# CPU_STM32F7.net
KiCad netlist of a schematic drawn in Altium Designer
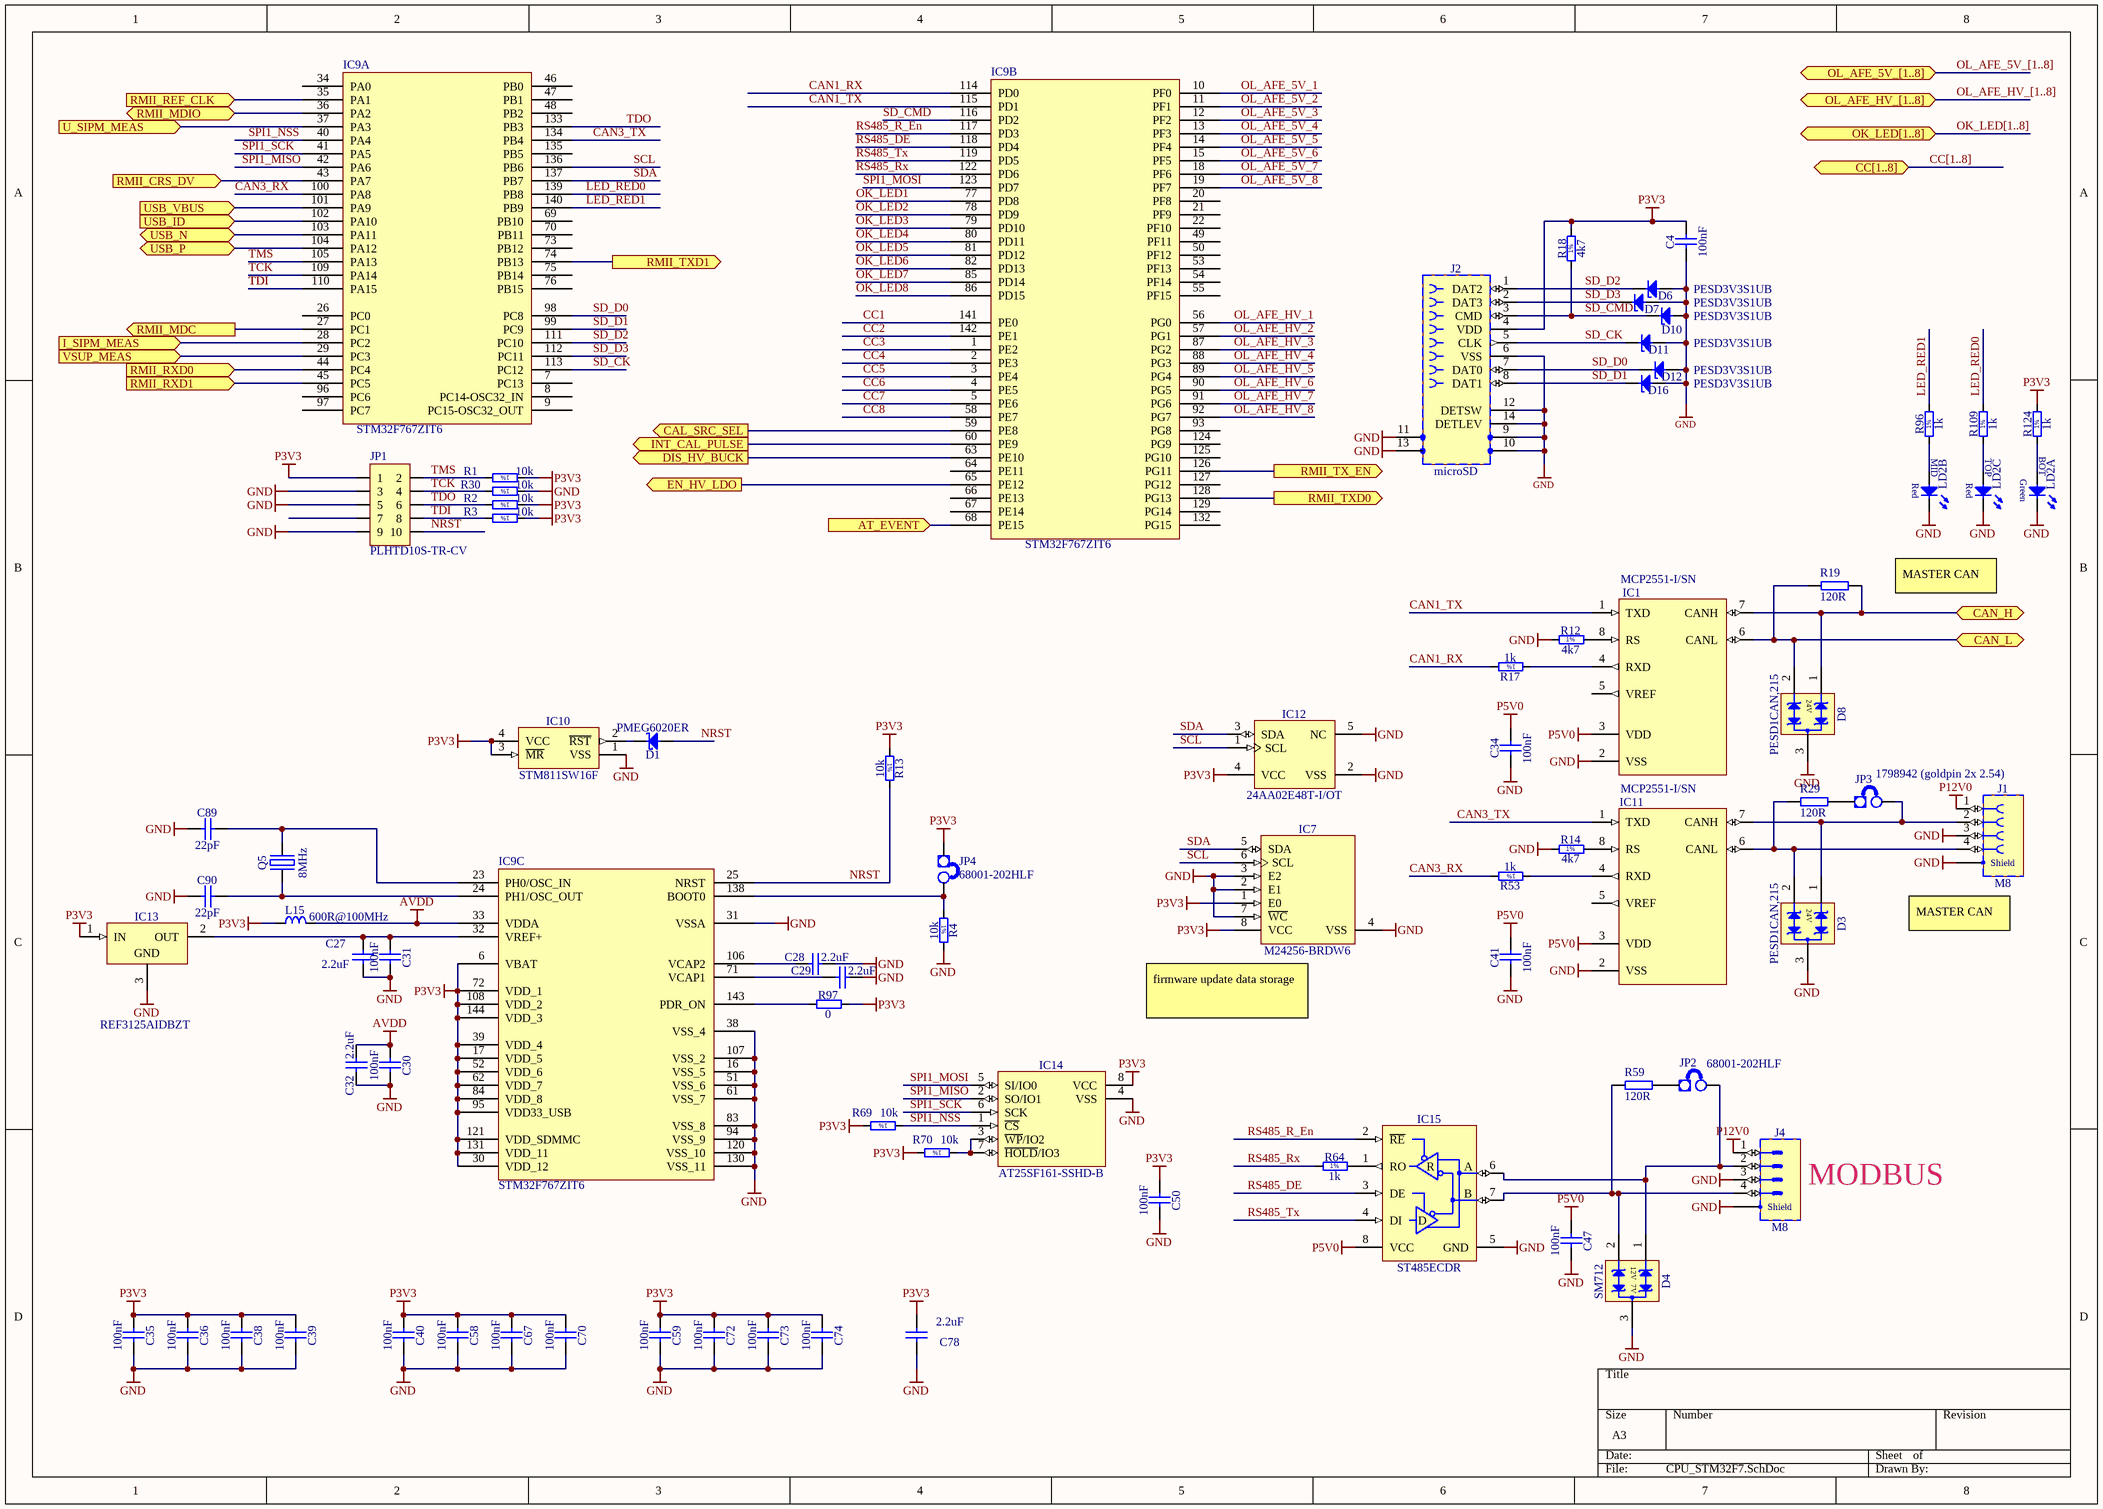
[diagram p0: CPU_STM32F7.SchDoc]

(export (version "E")
  (design (tool "Eeschema 10.0.6"))
  (components
    (comp (ref "C4")
      (value "100nF")
      (footprint "CAPC1005X55N")
      (description "Non-polarised capacitor")
      (fields
        (field (name "PART NUMBER") "CC0402_100NF_16V_10%_X7R")
        (field (name "VOLTAGE") "16V")
        (field (name "AUTHOR") "CERN DEM JLC")
      )
      (libsource (lib "Capacitors") (part "Capacitor - non polarized"))
    )
    (comp (ref "C27")
      (value "2.2uF")
      (footprint "CAPC1608X90N")
      (description "Non-polarised capacitor")
      (fields
        (field (name "PART NUMBER") "CC0603_2.2UF_10V_20%_X7R")
        (field (name "VOLTAGE") "10V")
        (field (name "AUTHOR") "CERN DEM JLC")
      )
      (libsource (lib "Capacitors") (part "Capacitor - non polarized"))
    )
    (comp (ref "C28")
      (value "2.2uF")
      (footprint "CAPC1608X90N")
      (description "Non-polarised capacitor")
      (fields
        (field (name "PART NUMBER") "CC0603_2.2UF_10V_20%_X7R")
        (field (name "VOLTAGE") "10V")
        (field (name "AUTHOR") "CERN DEM JLC")
      )
      (libsource (lib "Capacitors") (part "Capacitor - non polarized"))
    )
    (comp (ref "C29")
      (value "2.2uF")
      (footprint "CAPC1608X90N")
      (description "Non-polarised capacitor")
      (fields
        (field (name "PART NUMBER") "CC0603_2.2UF_10V_20%_X7R")
        (field (name "VOLTAGE") "10V")
        (field (name "AUTHOR") "CERN DEM JLC")
      )
      (libsource (lib "Capacitors") (part "Capacitor - non polarized"))
    )
    (comp (ref "C30")
      (value "100nF")
      (footprint "CAPC1005X55N")
      (description "Non-polarised capacitor")
      (fields
        (field (name "PART NUMBER") "CC0402_100NF_16V_10%_X7R")
        (field (name "VOLTAGE") "16V")
        (field (name "AUTHOR") "CERN DEM JLC")
      )
      (libsource (lib "Capacitors") (part "Capacitor - non polarized"))
    )
    (comp (ref "C31")
      (value "100nF")
      (footprint "CAPC1005X55N")
      (description "Non-polarised capacitor")
      (fields
        (field (name "PART NUMBER") "CC0402_100NF_16V_10%_X7R")
        (field (name "VOLTAGE") "16V")
        (field (name "AUTHOR") "CERN DEM JLC")
      )
      (libsource (lib "Capacitors") (part "Capacitor - non polarized"))
    )
    (comp (ref "C32")
      (value "2.2uF")
      (footprint "CAPC1608X90N")
      (description "Non-polarised capacitor")
      (fields
        (field (name "PART NUMBER") "CC0603_2.2UF_10V_20%_X7R")
        (field (name "VOLTAGE") "10V")
        (field (name "AUTHOR") "CERN DEM JLC")
      )
      (libsource (lib "Capacitors") (part "Capacitor - non polarized"))
    )
    (comp (ref "C34")
      (value "100nF")
      (footprint "CAPC1005X55N")
      (description "Non-polarised capacitor")
      (fields
        (field (name "PART NUMBER") "CC0402_100NF_16V_10%_X7R")
        (field (name "VOLTAGE") "16V")
        (field (name "AUTHOR") "CERN DEM JLC")
      )
      (libsource (lib "Capacitors") (part "Capacitor - non polarized"))
    )
    (comp (ref "C35")
      (value "100nF")
      (footprint "CAPC1005X55N")
      (description "Non-polarised capacitor")
      (fields
        (field (name "PART NUMBER") "CC0402_100NF_16V_10%_X7R")
        (field (name "VOLTAGE") "16V")
        (field (name "AUTHOR") "CERN DEM JLC")
      )
      (libsource (lib "Capacitors") (part "Capacitor - non polarized"))
    )
    (comp (ref "C36")
      (value "100nF")
      (footprint "CAPC1005X55N")
      (description "Non-polarised capacitor")
      (fields
        (field (name "PART NUMBER") "CC0402_100NF_16V_10%_X7R")
        (field (name "VOLTAGE") "16V")
        (field (name "AUTHOR") "CERN DEM JLC")
      )
      (libsource (lib "Capacitors") (part "Capacitor - non polarized"))
    )
    (comp (ref "C38")
      (value "100nF")
      (footprint "CAPC1005X55N")
      (description "Non-polarised capacitor")
      (fields
        (field (name "PART NUMBER") "CC0402_100NF_16V_10%_X7R")
        (field (name "VOLTAGE") "16V")
        (field (name "AUTHOR") "CERN DEM JLC")
      )
      (libsource (lib "Capacitors") (part "Capacitor - non polarized"))
    )
    (comp (ref "C39")
      (value "100nF")
      (footprint "CAPC1005X55N")
      (description "Non-polarised capacitor")
      (fields
        (field (name "PART NUMBER") "CC0402_100NF_16V_10%_X7R")
        (field (name "VOLTAGE") "16V")
        (field (name "AUTHOR") "CERN DEM JLC")
      )
      (libsource (lib "Capacitors") (part "Capacitor - non polarized"))
    )
    (comp (ref "C40")
      (value "100nF")
      (footprint "CAPC1005X55N")
      (description "Non-polarised capacitor")
      (fields
        (field (name "PART NUMBER") "CC0402_100NF_16V_10%_X7R")
        (field (name "VOLTAGE") "16V")
        (field (name "AUTHOR") "CERN DEM JLC")
      )
      (libsource (lib "Capacitors") (part "Capacitor - non polarized"))
    )
    (comp (ref "C41")
      (value "100nF")
      (footprint "CAPC1005X55N")
      (description "Non-polarised capacitor")
      (fields
        (field (name "PART NUMBER") "CC0402_100NF_16V_10%_X7R")
        (field (name "VOLTAGE") "16V")
        (field (name "AUTHOR") "CERN DEM JLC")
      )
      (libsource (lib "Capacitors") (part "Capacitor - non polarized"))
    )
    (comp (ref "C47")
      (value "100nF")
      (footprint "CAPC1005X55N")
      (description "Non-polarised capacitor")
      (fields
        (field (name "PART NUMBER") "CC0402_100NF_16V_10%_X7R")
        (field (name "VOLTAGE") "16V")
        (field (name "AUTHOR") "CERN DEM JLC")
      )
      (libsource (lib "Capacitors") (part "Capacitor - non polarized"))
    )
    (comp (ref "C50")
      (value "100nF")
      (footprint "CAPC1005X55N")
      (description "Non-polarised capacitor")
      (fields
        (field (name "PART NUMBER") "CC0402_100NF_16V_10%_X7R")
        (field (name "VOLTAGE") "16V")
        (field (name "AUTHOR") "CERN DEM JLC")
      )
      (libsource (lib "Capacitors") (part "Capacitor - non polarized"))
    )
    (comp (ref "C58")
      (value "100nF")
      (footprint "CAPC1005X55N")
      (description "Non-polarised capacitor")
      (fields
        (field (name "PART NUMBER") "CC0402_100NF_16V_10%_X7R")
        (field (name "VOLTAGE") "16V")
        (field (name "AUTHOR") "CERN DEM JLC")
      )
      (libsource (lib "Capacitors") (part "Capacitor - non polarized"))
    )
    (comp (ref "C59")
      (value "100nF")
      (footprint "CAPC1005X55N")
      (description "Non-polarised capacitor")
      (fields
        (field (name "PART NUMBER") "CC0402_100NF_16V_10%_X7R")
        (field (name "VOLTAGE") "16V")
        (field (name "AUTHOR") "CERN DEM JLC")
      )
      (libsource (lib "Capacitors") (part "Capacitor - non polarized"))
    )
    (comp (ref "C67")
      (value "100nF")
      (footprint "CAPC1005X55N")
      (description "Non-polarised capacitor")
      (fields
        (field (name "PART NUMBER") "CC0402_100NF_16V_10%_X7R")
        (field (name "VOLTAGE") "16V")
        (field (name "AUTHOR") "CERN DEM JLC")
      )
      (libsource (lib "Capacitors") (part "Capacitor - non polarized"))
    )
    (comp (ref "C70")
      (value "100nF")
      (footprint "CAPC1005X55N")
      (description "Non-polarised capacitor")
      (fields
        (field (name "PART NUMBER") "CC0402_100NF_16V_10%_X7R")
        (field (name "VOLTAGE") "16V")
        (field (name "AUTHOR") "CERN DEM JLC")
      )
      (libsource (lib "Capacitors") (part "Capacitor - non polarized"))
    )
    (comp (ref "C72")
      (value "100nF")
      (footprint "CAPC1005X55N")
      (description "Non-polarised capacitor")
      (fields
        (field (name "PART NUMBER") "CC0402_100NF_16V_10%_X7R")
        (field (name "VOLTAGE") "16V")
        (field (name "AUTHOR") "CERN DEM JLC")
      )
      (libsource (lib "Capacitors") (part "Capacitor - non polarized"))
    )
    (comp (ref "C73")
      (value "100nF")
      (footprint "CAPC1005X55N")
      (description "Non-polarised capacitor")
      (fields
        (field (name "PART NUMBER") "CC0402_100NF_16V_10%_X7R")
        (field (name "VOLTAGE") "16V")
        (field (name "AUTHOR") "CERN DEM JLC")
      )
      (libsource (lib "Capacitors") (part "Capacitor - non polarized"))
    )
    (comp (ref "C74")
      (value "100nF")
      (footprint "CAPC1005X55N")
      (description "Non-polarised capacitor")
      (fields
        (field (name "PART NUMBER") "CC0402_100NF_16V_10%_X7R")
        (field (name "VOLTAGE") "16V")
        (field (name "AUTHOR") "CERN DEM JLC")
      )
      (libsource (lib "Capacitors") (part "Capacitor - non polarized"))
    )
    (comp (ref "C78")
      (value "2.2uF")
      (footprint "CAPC1608X90N")
      (description "Non-polarised capacitor")
      (fields
        (field (name "PART NUMBER") "CC0603_2.2UF_10V_20%_X7R")
        (field (name "VOLTAGE") "10V")
        (field (name "AUTHOR") "CERN DEM JLC")
      )
      (libsource (lib "Capacitors") (part "Capacitor - non polarized"))
    )
    (comp (ref "C89")
      (value "22pF")
      (footprint "CAPC1005X55N")
      (description "Non-polarised capacitor")
      (fields
        (field (name "PART NUMBER") "CC0402_22PF_50V_5%_C0G")
        (field (name "VOLTAGE") "50V")
        (field (name "AUTHOR") "CERN DEM JLC")
      )
      (libsource (lib "Capacitors") (part "Capacitor - non polarized"))
    )
    (comp (ref "C90")
      (value "22pF")
      (footprint "CAPC1005X55N")
      (description "Non-polarised capacitor")
      (fields
        (field (name "PART NUMBER") "CC0402_22PF_50V_5%_C0G")
        (field (name "VOLTAGE") "50V")
        (field (name "AUTHOR") "CERN DEM JLC")
      )
      (libsource (lib "Capacitors") (part "Capacitor - non polarized"))
    )
    (comp (ref "D1")
      (value "PMEG6020ER")
      (footprint "SODFL3517X110N")
      (description "Schottky Diode")
      (fields
        (field (name "VOLTAGE") "60V")
        (field (name "POWER") "2A")
        (field (name "AUTHOR") "CERN DEM JMW")
      )
      (libsource (lib "ICs And Semiconductors") (part "Diode Schottky"))
    )
    (comp (ref "D3")
      (value "PESD1CAN,215")
      (footprint "SOT95P237X112-3N")
      (description "TVS Diode for CAN")
      (fields
        (field (name "VOLTAGE") "24V")
        (field (name "POWER") "400W")
        (field (name "AUTHOR") "CERN DEM JLC")
      )
      (libsource (lib "Diodes") (part "D_TVS_PESD1CAN"))
    )
    (comp (ref "D4")
      (value "SM712")
      (footprint "SOT95P237X112-3N")
      (description "Asymmetrical TVS Diode for Extended Common-Mode RS-485")
      (fields
        (field (name "VOLTAGE") "12V/-7V")
        (field (name "POWER") "400W")
        (field (name "AUTHOR") "CERN DEM JLC")
      )
      (libsource (lib "ICs And Semiconductors") (part "SM712"))
    )
    (comp (ref "D6")
      (value "PESD3V3S1UB")
      (footprint "SODFL1608X65N")
      (description "ESD protection diode")
      (fields
        (field (name "VOLTAGE") "3V3")
        (field (name "POWER") "330W")
        (field (name "AUTHOR") "CERN DEM JLC")
      )
      (libsource (lib "ICs And Semiconductors") (part "Diode ESD"))
    )
    (comp (ref "D7")
      (value "PESD3V3S1UB")
      (footprint "SODFL1608X65N")
      (description "ESD protection diode")
      (fields
        (field (name "VOLTAGE") "3V3")
        (field (name "POWER") "330W")
        (field (name "AUTHOR") "CERN DEM JLC")
      )
      (libsource (lib "ICs And Semiconductors") (part "Diode ESD"))
    )
    (comp (ref "D8")
      (value "PESD1CAN,215")
      (footprint "SOT95P237X112-3N")
      (description "TVS Diode for CAN")
      (fields
        (field (name "VOLTAGE") "24V")
        (field (name "POWER") "400W")
        (field (name "AUTHOR") "CERN DEM JLC")
      )
      (libsource (lib "Diodes") (part "D_TVS_PESD1CAN"))
    )
    (comp (ref "D10")
      (value "PESD3V3S1UB")
      (footprint "SODFL1608X65N")
      (description "ESD protection diode")
      (fields
        (field (name "VOLTAGE") "3V3")
        (field (name "POWER") "330W")
        (field (name "AUTHOR") "CERN DEM JLC")
      )
      (libsource (lib "ICs And Semiconductors") (part "Diode ESD"))
    )
    (comp (ref "D11")
      (value "PESD3V3S1UB")
      (footprint "SODFL1608X65N")
      (description "ESD protection diode")
      (fields
        (field (name "VOLTAGE") "3V3")
        (field (name "POWER") "330W")
        (field (name "AUTHOR") "CERN DEM JLC")
      )
      (libsource (lib "ICs And Semiconductors") (part "Diode ESD"))
    )
    (comp (ref "D12")
      (value "PESD3V3S1UB")
      (footprint "SODFL1608X65N")
      (description "ESD protection diode")
      (fields
        (field (name "VOLTAGE") "3V3")
        (field (name "POWER") "330W")
        (field (name "AUTHOR") "CERN DEM JLC")
      )
      (libsource (lib "ICs And Semiconductors") (part "Diode ESD"))
    )
    (comp (ref "D16")
      (value "PESD3V3S1UB")
      (footprint "SODFL1608X65N")
      (description "ESD protection diode")
      (fields
        (field (name "VOLTAGE") "3V3")
        (field (name "POWER") "330W")
        (field (name "AUTHOR") "CERN DEM JLC")
      )
      (libsource (lib "ICs And Semiconductors") (part "Diode ESD"))
    )
    (comp (ref "IC1")
      (value "MCP2551-I/SN")
      (footprint "SOIC127P600X175-8N")
      (description "High-Speed CAN Transceiver, 8-Pin SOIC, Industrial Temperature")
      (fields (field (name "MANUFACTURER") "MICROCHIP TECHNOLOGY") (field (name "AUTHOR") "GK"))
      (libsource (lib "LIBRARY_SCH") (part "IFC_MCP2551"))
    )
    (comp (ref "IC7")
      (value "M24256-BRDW6")
      (footprint "SOP65P640X120-8N")
      (description "256-Kbit Serial I²C Bus EEPROM")
      (fields
        (field (name "PART NUMBER") "M24256-BRDW6P")
        (field (name "MANUFACTURER") "ST MICROELECTRONICS")
        (field (name "AUTHOR") "CERN DEM MR")
      )
      (libsource (lib "LIBRARY_SCH") (part "MEM_M24256-BRDW6P"))
    )
    (comp (ref "IC9")
      (value "STM32F767ZIT6")
      (footprint "TSQFP50P2200X2200X160-144N")
      (description "32-bit Arm® Cortex-M7 216MHz MCUs, 2MB Flash,\r\n512kB RAM, 28 com. and analog interfaces")
      (libsource (lib "ICS_CPU") (part "UPC_STM32F767ZIT6"))
    )
    (comp (ref "IC10")
      (value "STM811SW16F")
      (footprint "SOT143N")
      (description "Microprocessor Reset Circuit")
      (fields (field (name "MANUFACTURER") "ST MICROELECTRONICS") (field (name "AUTHOR") "CERN DEM JLC"))
      (libsource (lib "ICs And Semiconductors") (part "STM811"))
    )
    (comp (ref "IC11")
      (value "MCP2551-I/SN")
      (footprint "SOIC127P600X175-8N")
      (description "High-Speed CAN Transceiver, 8-Pin SOIC, Industrial Temperature")
      (fields (field (name "MANUFACTURER") "MICROCHIP TECHNOLOGY") (field (name "AUTHOR") "GK"))
      (libsource (lib "LIBRARY_SCH") (part "IFC_MCP2551"))
    )
    (comp (ref "IC12")
      (value "24AA02E48T-I/OT")
      (footprint "SOT95P280X145-5N")
      (description "1.7V-5.5V, 2K I2C Serial EEPROM With EUI-48 Node Identity")
      (fields (field (name "MANUFACTURER") "MICROCHIP TECHNOLOGY") (field (name "AUTHOR") "CERN DEM MR"))
      (libsource (lib "ICs And Semiconductors") (part "24AA02E48T-I/OT"))
    )
    (comp (ref "IC13")
      (value "REF3125AIDBZT")
      (footprint "SOT95P237X112-3N")
      (description "3-Terminal Regulator 1=IN 2=OUT 3=GND")
      (fields (field (name "MANUFACTURER") "TEXAS INSTRUMENTS") (field (name "AUTHOR") "CERN DEM MR"))
      (libsource (lib "ICs And Semiconductors") (part "REG3 1IN-2OUT-3GND"))
    )
    (comp (ref "IC14")
      (value "AT25SF161-SSHD-B")
      (footprint "SOIC127P790X216-8N")
      (description "16Mb, 3V, Multiple I/O Serial NOR Flash Memory")
      (fields (field (name "AUTHOR") "GK"))
      (libsource (lib "LIBRARY_SCH") (part "MEM_AT25SF161"))
    )
    (comp (ref "IC15")
      (value "ST485ECDR")
      (footprint "SOIC127P600X175-8N")
      (description "±15kV ESD-Protected, Low Power  RS-485/RS-422 Transceiver")
      (fields (field (name "MANUFACTURER") "ST MICROELECTRONICS") (field (name "AUTHOR") "CERN DEM MR"))
      (libsource (lib "ICs And Semiconductors") (part "ST485EC"))
    )
    (comp (ref "J1")
      (value "M8")
      (footprint "AMPHENOL_M8AS-04PFFR-SF8001")
      (description "Connector 4 Female + Shield")
      (fields
        (field (name "PART NUMBER") "AMPHENOL_M8AS-04PFFR-SF8001")
        (field (name "MANUFACTURER") "AMPHENOL")
        (field (name "AUTHOR") "CERN DEM MR")
      )
      (libsource (lib "Connectors") (part "Connector 4 Female + Shield"))
    )
    (comp (ref "J2")
      (value "microSD")
      (footprint "MOLEX_502570-0893")
      (description "Connector MicroSD 8 Pin")
      (fields
        (field (name "PART NUMBER") "MOLEX_502570-0893")
        (field (name "MANUFACTURER") "MOLEX")
        (field (name "AUTHOR") "CERN DEM JLC")
      )
      (libsource (lib "Connectors") (part "MOLEX_502570-0893"))
    )
    (comp (ref "J4")
      (value "M8")
      (footprint "AMPHENOL_M8AS-04PMMR-SF8001")
      (description "Connector 4 Male + Shield")
      (fields
        (field (name "PART NUMBER") "AMPHENOL_M8AS-04PMMR-SF8001")
        (field (name "MANUFACTURER") "AMPHENOL")
        (field (name "AUTHOR") "CERN DEM MR")
      )
      (libsource (lib "Connectors") (part "Connector 4 Male + Shield"))
    )
    (comp (ref "JP1")
      (value "PLHTD10S-TR-CV")
      (footprint "PLHTD10S-TR-CV")
      (description "1.27 mm dual row goldpin (Maritex)")
      (libsource (lib "LIBRARY_SCH") (part "CON_2x5 1.27 SMT Male"))
    )
    (comp (ref "JP2")
      (value "68001-202HLF")
      (footprint "jump")
      (description "Jumper")
      (libsource (lib "LIBRARY_SCH") (part "JUMPER"))
    )
    (comp (ref "JP3")
      (value "1798942 (goldpin 2x 2.54)")
      (footprint "jump")
      (description "Jumper")
      (libsource (lib "LIBRARY_SCH") (part "JUMPER"))
    )
    (comp (ref "JP4")
      (value "68001-202HLF")
      (footprint "jump")
      (description "Jumper")
      (libsource (lib "") (part "JUMPER_1"))
    )
    (comp (ref "L15")
      (value "600R@100MHz")
      (footprint "INDC1005X55N")
      (description "Inductor")
      (fields
        (field (name "PART NUMBER") "IND0402_MURATA_BLM15HD601SN1")
        (field (name "POWER") "300mA")
        (field (name "AUTHOR") "CERN DEM JLC")
      )
      (libsource (lib "Inductors & Transformers") (part "Inductor"))
    )
    (comp (ref "LD2")
      (value "Red/Red/Green")
      (footprint "LED_DIALIGHT_570-0100-112F")
      (description "LED x3  Top Red, Middle Red, Bottom Green")
      (fields
        (field (name "PART NUMBER") "LED_DIALIGHT_570-0100-112F")
        (field (name "MANUFACTURER") "DIALIGHT")
        (field (name "AUTHOR") "CERN DEM JLC")
      )
      (libsource (lib "ICs And Semiconductors") (part "LED x3 G-1C2A-BOT_R-3C4A_R-5C6A-TOP"))
    )
    (comp (ref "Q5")
      (value "8MHz")
      (footprint "XTAL_TXC_7A")
      (description "Quartz Crystal")
      (fields
        (field (name "PART NUMBER") "XTAL_8MHZ_TXC_7A-8.000MAAE-T")
        (field (name "MANUFACTURER") "TXC CORPORATION")
        (field (name "AUTHOR") "CERN DEM JLC")
      )
      (libsource (lib "ICs And Semiconductors") (part "Quartz Crystal"))
    )
    (comp (ref "R1")
      (value "10k")
      (footprint "RESC1005X40N")
      (description "Resistor - 1%")
      (fields
        (field (name "PART NUMBER") "R0402_10K_1%_0.0625W_100PPM")
        (field (name "POWER") "0.0625W")
        (field (name "AUTHOR") "CERN DEM JLC")
      )
      (libsource (lib "Resistors") (part "Resistor - 1%"))
    )
    (comp (ref "R2")
      (value "10k")
      (footprint "RESC1005X40N")
      (description "Resistor - 1%")
      (fields
        (field (name "PART NUMBER") "R0402_10K_1%_0.0625W_100PPM")
        (field (name "POWER") "0.0625W")
        (field (name "AUTHOR") "CERN DEM JLC")
      )
      (libsource (lib "Resistors") (part "Resistor - 1%"))
    )
    (comp (ref "R3")
      (value "10k")
      (footprint "RESC1005X40N")
      (description "Resistor - 1%")
      (fields
        (field (name "PART NUMBER") "R0402_10K_1%_0.0625W_100PPM")
        (field (name "POWER") "0.0625W")
        (field (name "AUTHOR") "CERN DEM JLC")
      )
      (libsource (lib "Resistors") (part "Resistor - 1%"))
    )
    (comp (ref "R4")
      (value "10k")
      (footprint "RESC1005X40N")
      (description "Resistor - 1%")
      (fields
        (field (name "PART NUMBER") "R0402_10K_1%_0.0625W_100PPM")
        (field (name "POWER") "0.0625W")
        (field (name "AUTHOR") "CERN DEM JLC")
      )
      (libsource (lib "Resistors") (part "Resistor - 1%"))
    )
    (comp (ref "R12")
      (value "4k7")
      (footprint "RESC1005X40N")
      (description "Resistor - 1%")
      (fields
        (field (name "PART NUMBER") "R0402_4K7_1%_0.0625W_100PPM")
        (field (name "POWER") "0.0625W")
        (field (name "AUTHOR") "CERN DEM JLC")
      )
      (libsource (lib "Resistors") (part "Resistor - 1%"))
    )
    (comp (ref "R13")
      (value "10k")
      (footprint "RESC1005X40N")
      (description "Resistor - 1%")
      (fields
        (field (name "PART NUMBER") "R0402_10K_1%_0.0625W_100PPM")
        (field (name "POWER") "0.0625W")
        (field (name "AUTHOR") "CERN DEM JLC")
      )
      (libsource (lib "Resistors") (part "Resistor - 1%"))
    )
    (comp (ref "R14")
      (value "4k7")
      (footprint "RESC1005X40N")
      (description "Resistor - 1%")
      (fields
        (field (name "PART NUMBER") "R0402_4K7_1%_0.0625W_100PPM")
        (field (name "POWER") "0.0625W")
        (field (name "AUTHOR") "CERN DEM JLC")
      )
      (libsource (lib "Resistors") (part "Resistor - 1%"))
    )
    (comp (ref "R17")
      (value "1k")
      (footprint "RESC1005X40N")
      (description "Resistor - 1%")
      (fields
        (field (name "PART NUMBER") "R0402_1K_1%_0.0625W_100PPM")
        (field (name "POWER") "0.0625W")
        (field (name "AUTHOR") "CERN DEM JLC")
      )
      (libsource (lib "Resistors") (part "Resistor - 1%"))
    )
    (comp (ref "R18")
      (value "4k7")
      (footprint "RESC1005X40N")
      (description "Resistor - 1%")
      (fields
        (field (name "PART NUMBER") "R0402_4K7_1%_0.0625W_100PPM")
        (field (name "POWER") "0.0625W")
        (field (name "AUTHOR") "CERN DEM JLC")
      )
      (libsource (lib "Resistors") (part "Resistor - 1%"))
    )
    (comp (ref "R19")
      (value "120R")
      (footprint "1206R")
      (description "SMD Resistor")
      (libsource (lib "LIBRARY_SCH") (part "RES_1206"))
    )
    (comp (ref "R29")
      (value "120R")
      (footprint "1206R")
      (description "SMD Resistor")
      (libsource (lib "LIBRARY_SCH") (part "RES_1206"))
    )
    (comp (ref "R30")
      (value "10k")
      (footprint "RESC1005X40N")
      (description "Resistor - 1%")
      (fields
        (field (name "PART NUMBER") "R0402_10K_1%_0.0625W_100PPM")
        (field (name "POWER") "0.0625W")
        (field (name "AUTHOR") "CERN DEM JLC")
      )
      (libsource (lib "Resistors") (part "Resistor - 1%"))
    )
    (comp (ref "R53")
      (value "1k")
      (footprint "RESC1005X40N")
      (description "Resistor - 1%")
      (fields
        (field (name "PART NUMBER") "R0402_1K_1%_0.0625W_100PPM")
        (field (name "POWER") "0.0625W")
        (field (name "AUTHOR") "CERN DEM JLC")
      )
      (libsource (lib "Resistors") (part "Resistor - 1%"))
    )
    (comp (ref "R59")
      (value "120R")
      (footprint "1206R")
      (description "SMD Resistor")
      (libsource (lib "LIBRARY_SCH") (part "RES_1206"))
    )
    (comp (ref "R64")
      (value "1k")
      (footprint "RESC1005X40N")
      (description "Resistor - 1%")
      (fields
        (field (name "PART NUMBER") "R0402_1K_1%_0.0625W_100PPM")
        (field (name "POWER") "0.0625W")
        (field (name "AUTHOR") "CERN DEM JLC")
      )
      (libsource (lib "Resistors") (part "Resistor - 1%"))
    )
    (comp (ref "R69")
      (value "10k")
      (footprint "RESC1005X40N")
      (description "Resistor - 1%")
      (fields
        (field (name "PART NUMBER") "R0402_10K_1%_0.0625W_100PPM")
        (field (name "POWER") "0.0625W")
        (field (name "AUTHOR") "CERN DEM JLC")
      )
      (libsource (lib "Resistors") (part "Resistor - 1%"))
    )
    (comp (ref "R70")
      (value "10k")
      (footprint "RESC1005X40N")
      (description "Resistor - 1%")
      (fields
        (field (name "PART NUMBER") "R0402_10K_1%_0.0625W_100PPM")
        (field (name "POWER") "0.0625W")
        (field (name "AUTHOR") "CERN DEM JLC")
      )
      (libsource (lib "Resistors") (part "Resistor - 1%"))
    )
    (comp (ref "R96")
      (value "1k")
      (footprint "RESC1005X40N")
      (description "Resistor - 1%")
      (fields
        (field (name "PART NUMBER") "R0402_1K_1%_0.0625W_100PPM")
        (field (name "POWER") "0.0625W")
        (field (name "AUTHOR") "CERN DEM JLC")
      )
      (libsource (lib "Resistors") (part "Resistor - 1%"))
    )
    (comp (ref "R97")
      (value "0")
      (footprint "RESC1608X55N")
      (description "Resistor")
      (fields
        (field (name "PART NUMBER") "R0603_0R_JUMPER")
        (field (name "MANUFACTURER") "GENERIC")
        (field (name "AUTHOR") "CERN DEM JLC")
      )
      (libsource (lib "Resistors") (part "Resistor"))
    )
    (comp (ref "R109")
      (value "1k")
      (footprint "RESC1005X40N")
      (description "Resistor - 1%")
      (fields
        (field (name "PART NUMBER") "R0402_1K_1%_0.0625W_100PPM")
        (field (name "POWER") "0.0625W")
        (field (name "AUTHOR") "CERN DEM JLC")
      )
      (libsource (lib "Resistors") (part "Resistor - 1%"))
    )
    (comp (ref "R124")
      (value "1k")
      (footprint "RESC1005X40N")
      (description "Resistor - 1%")
      (fields
        (field (name "PART NUMBER") "R0402_1K_1%_0.0625W_100PPM")
        (field (name "POWER") "0.0625W")
        (field (name "AUTHOR") "CERN DEM JLC")
      )
      (libsource (lib "Resistors") (part "Resistor - 1%"))
    )
  )
  (nets
    (net (code "1") (name "/AT_EVENT") (class "Default")
      (node (ref "IC9") (pin "68") (pinfunction "PE15_68") (pintype "passive"))
    )
    (net (code "2") (name "/CAL_SRC_SEL") (class "Default")
      (node (ref "IC9") (pin "59") (pinfunction "PE8_59") (pintype "passive"))
    )
    (net (code "3") (name "/CAN1_RX") (class "Default")
      (node (ref "IC9") (pin "114") (pinfunction "PD0_114") (pintype "passive"))
      (node (ref "R17") (pin "2") (pinfunction "2_2") (pintype "passive"))
    )
    (net (code "4") (name "/CAN1_TX") (class "Default")
      (node (ref "IC1") (pin "1") (pinfunction "TXD_1") (pintype "input"))
      (node (ref "IC9") (pin "115") (pinfunction "PD1_115") (pintype "passive"))
    )
    (net (code "5") (name "/CAN3_RX") (class "Default")
      (node (ref "IC9") (pin "100") (pinfunction "PA8_100") (pintype "passive"))
      (node (ref "R53") (pin "2") (pinfunction "2_2") (pintype "passive"))
    )
    (net (code "6") (name "/CAN3_TX") (class "Default")
      (node (ref "IC11") (pin "1") (pinfunction "TXD_1") (pintype "input"))
      (node (ref "IC9") (pin "134") (pinfunction "PB4_134") (pintype "passive"))
    )
    (net (code "7") (name "/CAN_H") (class "Default")
      (node (ref "D8") (pin "1") (pinfunction "I/O1_1") (pintype "passive"))
      (node (ref "IC1") (pin "7") (pinfunction "CANH_7") (pintype "bidirectional"))
      (node (ref "R19") (pin "2") (pinfunction "2_2") (pintype "passive"))
    )
    (net (code "8") (name "/CAN_L") (class "Default")
      (node (ref "D8") (pin "2") (pinfunction "I/O2_2") (pintype "passive"))
      (node (ref "IC1") (pin "6") (pinfunction "CANL_6") (pintype "bidirectional"))
      (node (ref "R19") (pin "1") (pinfunction "1_1") (pintype "passive"))
    )
    (net (code "9") (name "/CC1") (class "Default")
      (node (ref "IC9") (pin "141") (pinfunction "PE0_141") (pintype "passive"))
    )
    (net (code "10") (name "/CC2") (class "Default")
      (node (ref "IC9") (pin "142") (pinfunction "PE1_142") (pintype "passive"))
    )
    (net (code "11") (name "/CC3") (class "Default")
      (node (ref "IC9") (pin "1") (pinfunction "PE2_1") (pintype "passive"))
    )
    (net (code "12") (name "/CC4") (class "Default")
      (node (ref "IC9") (pin "2") (pinfunction "PE3_2") (pintype "passive"))
    )
    (net (code "13") (name "/CC5") (class "Default")
      (node (ref "IC9") (pin "3") (pinfunction "PE4_3") (pintype "passive"))
    )
    (net (code "14") (name "/CC6") (class "Default")
      (node (ref "IC9") (pin "4") (pinfunction "PE5_4") (pintype "passive"))
    )
    (net (code "15") (name "/CC7") (class "Default")
      (node (ref "IC9") (pin "5") (pinfunction "PE6_5") (pintype "passive"))
    )
    (net (code "16") (name "/CC8") (class "Default")
      (node (ref "IC9") (pin "58") (pinfunction "PE7_58") (pintype "passive"))
    )
    (net (code "18") (name "/DIS_HV_BUCK") (class "Default")
      (node (ref "IC9") (pin "63") (pinfunction "PE10_63") (pintype "passive"))
    )
    (net (code "19") (name "/EN_HV_LDO") (class "Default")
      (node (ref "IC9") (pin "65") (pinfunction "PE12_65") (pintype "passive"))
    )
    (net (code "20") (name "/INT_CAL_PULSE") (class "Default")
      (node (ref "IC9") (pin "60") (pinfunction "PE9_60") (pintype "passive"))
    )
    (net (code "21") (name "/I_SIPM_MEAS") (class "Default")
      (node (ref "IC9") (pin "28") (pinfunction "PC2_28") (pintype "passive"))
    )
    (net (code "22") (name "/LED_RED0") (class "Default")
      (node (ref "IC9") (pin "139") (pinfunction "PB8_139") (pintype "passive"))
      (node (ref "R109") (pin "2") (pinfunction "2_2") (pintype "passive"))
    )
    (net (code "23") (name "/LED_RED1") (class "Default")
      (node (ref "IC9") (pin "140") (pinfunction "PB9_140") (pintype "passive"))
      (node (ref "R96") (pin "2") (pinfunction "2_2") (pintype "passive"))
    )
    (net (code "24") (name "/NRST") (class "Default")
      (node (ref "D1") (pin "2") (pinfunction "A_2") (pintype "passive"))
      (node (ref "IC9") (pin "25") (pinfunction "NRST_25") (pintype "passive"))
      (node (ref "JP1") (pin "10") (pinfunction "10_10") (pintype "passive"))
      (node (ref "R13") (pin "2") (pinfunction "2_2") (pintype "passive"))
    )
    (net (code "25") (name "/OK_LED1") (class "Default")
      (node (ref "IC9") (pin "77") (pinfunction "PD8_77") (pintype "passive"))
    )
    (net (code "26") (name "/OK_LED2") (class "Default")
      (node (ref "IC9") (pin "78") (pinfunction "PD9_78") (pintype "passive"))
    )
    (net (code "27") (name "/OK_LED3") (class "Default")
      (node (ref "IC9") (pin "79") (pinfunction "PD10_79") (pintype "passive"))
    )
    (net (code "28") (name "/OK_LED4") (class "Default")
      (node (ref "IC9") (pin "80") (pinfunction "PD11_80") (pintype "passive"))
    )
    (net (code "29") (name "/OK_LED5") (class "Default")
      (node (ref "IC9") (pin "81") (pinfunction "PD12_81") (pintype "passive"))
    )
    (net (code "30") (name "/OK_LED6") (class "Default")
      (node (ref "IC9") (pin "82") (pinfunction "PD13_82") (pintype "passive"))
    )
    (net (code "31") (name "/OK_LED7") (class "Default")
      (node (ref "IC9") (pin "85") (pinfunction "PD14_85") (pintype "passive"))
    )
    (net (code "32") (name "/OK_LED8") (class "Default")
      (node (ref "IC9") (pin "86") (pinfunction "PD15_86") (pintype "passive"))
    )
    (net (code "34") (name "/OL_AFE_5V_1") (class "Default")
      (node (ref "IC9") (pin "10") (pinfunction "PF0_10") (pintype "passive"))
    )
    (net (code "35") (name "/OL_AFE_5V_2") (class "Default")
      (node (ref "IC9") (pin "11") (pinfunction "PF1_11") (pintype "passive"))
    )
    (net (code "36") (name "/OL_AFE_5V_3") (class "Default")
      (node (ref "IC9") (pin "12") (pinfunction "PF2_12") (pintype "passive"))
    )
    (net (code "37") (name "/OL_AFE_5V_4") (class "Default")
      (node (ref "IC9") (pin "13") (pinfunction "PF3_13") (pintype "passive"))
    )
    (net (code "38") (name "/OL_AFE_5V_5") (class "Default")
      (node (ref "IC9") (pin "14") (pinfunction "PF4_14") (pintype "passive"))
    )
    (net (code "39") (name "/OL_AFE_5V_6") (class "Default")
      (node (ref "IC9") (pin "15") (pinfunction "PF5_15") (pintype "passive"))
    )
    (net (code "40") (name "/OL_AFE_5V_7") (class "Default")
      (node (ref "IC9") (pin "18") (pinfunction "PF6_18") (pintype "passive"))
    )
    (net (code "41") (name "/OL_AFE_5V_8") (class "Default")
      (node (ref "IC9") (pin "19") (pinfunction "PF7_19") (pintype "passive"))
    )
    (net (code "43") (name "/OL_AFE_HV_1") (class "Default")
      (node (ref "IC9") (pin "56") (pinfunction "PG0_56") (pintype "passive"))
    )
    (net (code "44") (name "/OL_AFE_HV_2") (class "Default")
      (node (ref "IC9") (pin "57") (pinfunction "PG1_57") (pintype "passive"))
    )
    (net (code "45") (name "/OL_AFE_HV_3") (class "Default")
      (node (ref "IC9") (pin "87") (pinfunction "PG2_87") (pintype "passive"))
    )
    (net (code "46") (name "/OL_AFE_HV_4") (class "Default")
      (node (ref "IC9") (pin "88") (pinfunction "PG3_88") (pintype "passive"))
    )
    (net (code "47") (name "/OL_AFE_HV_5") (class "Default")
      (node (ref "IC9") (pin "89") (pinfunction "PG4_89") (pintype "passive"))
    )
    (net (code "48") (name "/OL_AFE_HV_6") (class "Default")
      (node (ref "IC9") (pin "90") (pinfunction "PG5_90") (pintype "passive"))
    )
    (net (code "49") (name "/OL_AFE_HV_7") (class "Default")
      (node (ref "IC9") (pin "91") (pinfunction "PG6_91") (pintype "passive"))
    )
    (net (code "50") (name "/OL_AFE_HV_8") (class "Default")
      (node (ref "IC9") (pin "92") (pinfunction "PG7_92") (pintype "passive"))
    )
    (net (code "52") (name "/RMII_CRS_DV") (class "Default")
      (node (ref "IC9") (pin "43") (pinfunction "PA7_43") (pintype "passive"))
    )
    (net (code "53") (name "/RMII_MDC") (class "Default")
      (node (ref "IC9") (pin "27") (pinfunction "PC1_27") (pintype "passive"))
    )
    (net (code "54") (name "/RMII_MDIO") (class "Default")
      (node (ref "IC9") (pin "36") (pinfunction "PA2_36") (pintype "passive"))
    )
    (net (code "55") (name "/RMII_REF_CLK") (class "Default")
      (node (ref "IC9") (pin "35") (pinfunction "PA1_35") (pintype "passive"))
    )
    (net (code "56") (name "/RMII_RXD0") (class "Default")
      (node (ref "IC9") (pin "44") (pinfunction "PC4_44") (pintype "passive"))
    )
    (net (code "57") (name "/RMII_RXD1") (class "Default")
      (node (ref "IC9") (pin "45") (pinfunction "PC5_45") (pintype "passive"))
    )
    (net (code "58") (name "/RMII_TXD0") (class "Default")
      (node (ref "IC9") (pin "128") (pinfunction "PG13_128") (pintype "passive"))
    )
    (net (code "59") (name "/RMII_TXD1") (class "Default")
      (node (ref "IC9") (pin "74") (pinfunction "PB13_74") (pintype "passive"))
    )
    (net (code "60") (name "/RMII_TX_EN") (class "Default")
      (node (ref "IC9") (pin "126") (pinfunction "PG11_126") (pintype "passive"))
    )
    (net (code "61") (name "/RS485_DE") (class "Default")
      (node (ref "IC15") (pin "3") (pinfunction "DE_3") (pintype "input"))
      (node (ref "IC9") (pin "118") (pinfunction "PD4_118") (pintype "passive"))
    )
    (net (code "62") (name "/RS485_R_En") (class "Default")
      (node (ref "IC15") (pin "2") (pinfunction "~{RE}_2") (pintype "input"))
      (node (ref "IC9") (pin "117") (pinfunction "PD3_117") (pintype "passive"))
    )
    (net (code "63") (name "/RS485_Rx") (class "Default")
      (node (ref "IC9") (pin "122") (pinfunction "PD6_122") (pintype "passive"))
      (node (ref "R64") (pin "1") (pinfunction "1_1") (pintype "passive"))
    )
    (net (code "64") (name "/RS485_Tx") (class "Default")
      (node (ref "IC15") (pin "4") (pinfunction "DI_4") (pintype "input"))
      (node (ref "IC9") (pin "119") (pinfunction "PD5_119") (pintype "passive"))
    )
    (net (code "65") (name "/SCL") (class "Default")
      (node (ref "IC12") (pin "1") (pinfunction "SCL_1") (pintype "input"))
      (node (ref "IC7") (pin "6") (pinfunction "SCL_6") (pintype "input"))
      (node (ref "IC9") (pin "136") (pinfunction "PB6_136") (pintype "passive"))
    )
    (net (code "66") (name "/SDA") (class "Default")
      (node (ref "IC12") (pin "3") (pinfunction "SDA_3") (pintype "bidirectional"))
      (node (ref "IC7") (pin "5") (pinfunction "SDA_5") (pintype "bidirectional"))
      (node (ref "IC9") (pin "137") (pinfunction "PB7_137") (pintype "passive"))
    )
    (net (code "67") (name "/SD_CK") (class "Default")
      (node (ref "D11") (pin "1") (pinfunction "C_1") (pintype "passive"))
      (node (ref "IC9") (pin "113") (pinfunction "PC12_113") (pintype "passive"))
      (node (ref "J2") (pin "5") (pinfunction "CLK_5") (pintype "output"))
    )
    (net (code "68") (name "/SD_CMD") (class "Default")
      (node (ref "D10") (pin "1") (pinfunction "C_1") (pintype "passive"))
      (node (ref "IC9") (pin "116") (pinfunction "PD2_116") (pintype "passive"))
      (node (ref "J2") (pin "3") (pinfunction "CMD_3") (pintype "bidirectional"))
      (node (ref "R18") (pin "1") (pinfunction "1_1") (pintype "passive"))
    )
    (net (code "69") (name "/SD_D0") (class "Default")
      (node (ref "D12") (pin "1") (pinfunction "C_1") (pintype "passive"))
      (node (ref "IC9") (pin "98") (pinfunction "PC8_98") (pintype "passive"))
      (node (ref "J2") (pin "7") (pinfunction "DAT0_7") (pintype "bidirectional"))
    )
    (net (code "70") (name "/SD_D1") (class "Default")
      (node (ref "D16") (pin "1") (pinfunction "C_1") (pintype "passive"))
      (node (ref "IC9") (pin "99") (pinfunction "PC9_99") (pintype "passive"))
      (node (ref "J2") (pin "8") (pinfunction "DAT1_8") (pintype "bidirectional"))
    )
    (net (code "71") (name "/SD_D2") (class "Default")
      (node (ref "D6") (pin "1") (pinfunction "C_1") (pintype "passive"))
      (node (ref "IC9") (pin "111") (pinfunction "PC10_111") (pintype "passive"))
      (node (ref "J2") (pin "1") (pinfunction "DAT2_1") (pintype "bidirectional"))
    )
    (net (code "72") (name "/SD_D3") (class "Default")
      (node (ref "D7") (pin "1") (pinfunction "C_1") (pintype "passive"))
      (node (ref "IC9") (pin "112") (pinfunction "PC11_112") (pintype "passive"))
      (node (ref "J2") (pin "2") (pinfunction "DAT3_2") (pintype "bidirectional"))
    )
    (net (code "73") (name "/SPI1_MISO") (class "Default")
      (node (ref "IC14") (pin "2") (pinfunction "SO/IO1_2") (pintype "bidirectional"))
      (node (ref "IC9") (pin "42") (pinfunction "PA6_42") (pintype "passive"))
    )
    (net (code "74") (name "/SPI1_MOSI") (class "Default")
      (node (ref "IC14") (pin "5") (pinfunction "SI/IO0_5") (pintype "bidirectional"))
      (node (ref "IC9") (pin "123") (pinfunction "PD7_123") (pintype "passive"))
    )
    (net (code "75") (name "/SPI1_NSS") (class "Default")
      (node (ref "IC14") (pin "1") (pinfunction "~{CS}_1") (pintype "input"))
      (node (ref "IC9") (pin "40") (pinfunction "PA4_40") (pintype "passive"))
      (node (ref "R69") (pin "1") (pinfunction "1_1") (pintype "passive"))
    )
    (net (code "76") (name "/SPI1_SCK") (class "Default")
      (node (ref "IC14") (pin "6") (pinfunction "SCK_6") (pintype "input"))
      (node (ref "IC9") (pin "41") (pinfunction "PA5_41") (pintype "passive"))
    )
    (net (code "77") (name "/TCK") (class "Default")
      (node (ref "IC9") (pin "109") (pinfunction "PA14_109") (pintype "passive"))
      (node (ref "JP1") (pin "4") (pinfunction "4_4") (pintype "passive"))
      (node (ref "R30") (pin "2") (pinfunction "2_2") (pintype "passive"))
    )
    (net (code "78") (name "/TDI") (class "Default")
      (node (ref "IC9") (pin "110") (pinfunction "PA15_110") (pintype "passive"))
      (node (ref "JP1") (pin "8") (pinfunction "8_8") (pintype "passive"))
      (node (ref "R3") (pin "2") (pinfunction "2_2") (pintype "passive"))
    )
    (net (code "79") (name "/TDO") (class "Default")
      (node (ref "IC9") (pin "133") (pinfunction "PB3_133") (pintype "passive"))
      (node (ref "JP1") (pin "6") (pinfunction "6_6") (pintype "passive"))
      (node (ref "R2") (pin "2") (pinfunction "2_2") (pintype "passive"))
    )
    (net (code "80") (name "/TMS") (class "Default")
      (node (ref "IC9") (pin "105") (pinfunction "PA13_105") (pintype "passive"))
      (node (ref "JP1") (pin "2") (pinfunction "2_2") (pintype "passive"))
      (node (ref "R1") (pin "2") (pinfunction "2_2") (pintype "passive"))
    )
    (net (code "81") (name "/USB_ID") (class "Default")
      (node (ref "IC9") (pin "102") (pinfunction "PA10_102") (pintype "passive"))
    )
    (net (code "82") (name "/USB_N") (class "Default")
      (node (ref "IC9") (pin "103") (pinfunction "PA11_103") (pintype "passive"))
    )
    (net (code "83") (name "/USB_P") (class "Default")
      (node (ref "IC9") (pin "104") (pinfunction "PA12_104") (pintype "passive"))
    )
    (net (code "84") (name "/USB_VBUS") (class "Default")
      (node (ref "IC9") (pin "101") (pinfunction "PA9_101") (pintype "passive"))
    )
    (net (code "85") (name "/U_SIPM_MEAS") (class "Default")
      (node (ref "IC9") (pin "37") (pinfunction "PA3_37") (pintype "passive"))
    )
    (net (code "86") (name "/VSUP_MEAS") (class "Default")
      (node (ref "IC9") (pin "29") (pinfunction "PC3_29") (pintype "passive"))
    )
    (net (code "87") (name "AVDD") (class "Default")
      (node (ref "C30") (pin "1") (pinfunction "1_1") (pintype "passive"))
      (node (ref "C32") (pin "2") (pinfunction "2_2") (pintype "passive"))
      (node (ref "IC9") (pin "33") (pinfunction "VDDA_33") (pintype "passive"))
      (node (ref "L15") (pin "2") (pinfunction "2_2") (pintype "passive"))
    )
    (net (code "88") (name "GND") (class "Default")
      (node (ref "C27") (pin "1") (pinfunction "1_1") (pintype "passive"))
      (node (ref "C28") (pin "2") (pinfunction "2_2") (pintype "passive"))
      (node (ref "C29") (pin "2") (pinfunction "2_2") (pintype "passive"))
      (node (ref "C30") (pin "2") (pinfunction "2_2") (pintype "passive"))
      (node (ref "C31") (pin "2") (pinfunction "2_2") (pintype "passive"))
      (node (ref "C32") (pin "1") (pinfunction "1_1") (pintype "passive"))
      (node (ref "C34") (pin "1") (pinfunction "1_1") (pintype "passive"))
      (node (ref "C35") (pin "2") (pinfunction "2_2") (pintype "passive"))
      (node (ref "C36") (pin "2") (pinfunction "2_2") (pintype "passive"))
      (node (ref "C38") (pin "2") (pinfunction "2_2") (pintype "passive"))
      (node (ref "C39") (pin "2") (pinfunction "2_2") (pintype "passive"))
      (node (ref "C4") (pin "1") (pinfunction "1_1") (pintype "passive"))
      (node (ref "C40") (pin "2") (pinfunction "2_2") (pintype "passive"))
      (node (ref "C41") (pin "1") (pinfunction "1_1") (pintype "passive"))
      (node (ref "C47") (pin "2") (pinfunction "2_2") (pintype "passive"))
      (node (ref "C50") (pin "2") (pinfunction "2_2") (pintype "passive"))
      (node (ref "C58") (pin "2") (pinfunction "2_2") (pintype "passive"))
      (node (ref "C59") (pin "2") (pinfunction "2_2") (pintype "passive"))
      (node (ref "C67") (pin "2") (pinfunction "2_2") (pintype "passive"))
      (node (ref "C70") (pin "2") (pinfunction "2_2") (pintype "passive"))
      (node (ref "C72") (pin "2") (pinfunction "2_2") (pintype "passive"))
      (node (ref "C73") (pin "2") (pinfunction "2_2") (pintype "passive"))
      (node (ref "C74") (pin "2") (pinfunction "2_2") (pintype "passive"))
      (node (ref "C78") (pin "1") (pinfunction "1_1") (pintype "passive"))
      (node (ref "C89") (pin "1") (pinfunction "1_1") (pintype "passive"))
      (node (ref "C90") (pin "1") (pinfunction "1_1") (pintype "passive"))
      (node (ref "D10") (pin "2") (pinfunction "A_2") (pintype "passive"))
      (node (ref "D11") (pin "2") (pinfunction "A_2") (pintype "passive"))
      (node (ref "D12") (pin "2") (pinfunction "A_2") (pintype "passive"))
      (node (ref "D16") (pin "2") (pinfunction "A_2") (pintype "passive"))
      (node (ref "D3") (pin "3") (pinfunction "GND_3") (pintype "passive"))
      (node (ref "D4") (pin "3") (pinfunction "GND_3") (pintype "passive"))
      (node (ref "D6") (pin "2") (pinfunction "A_2") (pintype "passive"))
      (node (ref "D7") (pin "2") (pinfunction "A_2") (pintype "passive"))
      (node (ref "D8") (pin "3") (pinfunction "GND_3") (pintype "passive"))
      (node (ref "IC1") (pin "2") (pinfunction "VSS_2") (pintype "power_in"))
      (node (ref "IC10") (pin "1") (pinfunction "VSS_1") (pintype "power_in"))
      (node (ref "IC11") (pin "2") (pinfunction "VSS_2") (pintype "power_in"))
      (node (ref "IC12") (pin "2") (pinfunction "VSS_2") (pintype "power_in"))
      (node (ref "IC12") (pin "5") (pinfunction "NC_5") (pintype "passive"))
      (node (ref "IC13") (pin "3") (pinfunction "GND_3") (pintype "power_in"))
      (node (ref "IC14") (pin "4") (pinfunction "VSS_4") (pintype "power_in"))
      (node (ref "IC15") (pin "5") (pinfunction "GND_5") (pintype "power_in"))
      (node (ref "IC7") (pin "2") (pinfunction "E1_2") (pintype "input"))
      (node (ref "IC7") (pin "3") (pinfunction "E2_3") (pintype "input"))
      (node (ref "IC7") (pin "4") (pinfunction "VSS_4") (pintype "power_in"))
      (node (ref "IC7") (pin "7") (pinfunction "~{WC}_7") (pintype "input"))
      (node (ref "IC9") (pin "107") (pinfunction "VSS_2_107") (pintype "passive"))
      (node (ref "IC9") (pin "120") (pinfunction "VSS_10_120") (pintype "passive"))
      (node (ref "IC9") (pin "130") (pinfunction "VSS_11_130") (pintype "passive"))
      (node (ref "IC9") (pin "16") (pinfunction "VSS_5_16") (pintype "passive"))
      (node (ref "IC9") (pin "31") (pinfunction "VSSA_31") (pintype "passive"))
      (node (ref "IC9") (pin "38") (pinfunction "VSS_4_38") (pintype "passive"))
      (node (ref "IC9") (pin "51") (pinfunction "VSS_6_51") (pintype "passive"))
      (node (ref "IC9") (pin "61") (pinfunction "VSS_7_61") (pintype "passive"))
      (node (ref "IC9") (pin "83") (pinfunction "VSS_8_83") (pintype "passive"))
      (node (ref "IC9") (pin "94") (pinfunction "VSS_9_94") (pintype "passive"))
      (node (ref "J1") (pin "3") (pinfunction "3_3") (pintype "bidirectional"))
      (node (ref "J1") (pin "SHIELD") (pinfunction "SHIELD_SHIELD") (pintype "passive"))
      (node (ref "J2") (pin "10") (pinfunction "10_10") (pintype "passive"))
      (node (ref "J2") (pin "11") (pinfunction "11_11") (pintype "passive"))
      (node (ref "J2") (pin "12") (pinfunction "DETSW_12") (pintype "passive"))
      (node (ref "J2") (pin "13") (pinfunction "13_13") (pintype "passive"))
      (node (ref "J2") (pin "14") (pinfunction "DETLEV_14") (pintype "passive"))
      (node (ref "J2") (pin "6") (pinfunction "VSS_6") (pintype "power_in"))
      (node (ref "J2") (pin "9") (pinfunction "9_9") (pintype "passive"))
      (node (ref "J4") (pin "3") (pinfunction "3_3") (pintype "bidirectional"))
      (node (ref "J4") (pin "SHIELD") (pinfunction "SHIELD_SHIELD") (pintype "passive"))
      (node (ref "JP1") (pin "3") (pinfunction "3_3") (pintype "passive"))
      (node (ref "JP1") (pin "5") (pinfunction "5_5") (pintype "passive"))
      (node (ref "JP1") (pin "9") (pinfunction "9_9") (pintype "passive"))
      (node (ref "LD2") (pin "2") (pinfunction "C_2") (pintype "passive"))
      (node (ref "LD2") (pin "4") (pinfunction "C_4") (pintype "passive"))
      (node (ref "LD2") (pin "6") (pinfunction "C_6") (pintype "passive"))
      (node (ref "R12") (pin "1") (pinfunction "1_1") (pintype "passive"))
      (node (ref "R14") (pin "1") (pinfunction "1_1") (pintype "passive"))
      (node (ref "R30") (pin "1") (pinfunction "1_1") (pintype "passive"))
      (node (ref "R4") (pin "2") (pinfunction "2_2") (pintype "passive"))
    )
    (net (code "89") (name "Net-(D1-C)") (class "Default")
      (node (ref "D1") (pin "1") (pinfunction "C_1") (pintype "passive"))
      (node (ref "IC10") (pin "2") (pinfunction "~{RST}_2") (pintype "output"))
    )
    (net (code "90") (name "Net-(D3-I{slash}O1)") (class "Default")
      (node (ref "D3") (pin "1") (pinfunction "I/O1_1") (pintype "passive"))
      (node (ref "IC11") (pin "7") (pinfunction "CANH_7") (pintype "bidirectional"))
      (node (ref "J1") (pin "2") (pinfunction "2_2") (pintype "bidirectional"))
      (node (ref "JP3") (pin "2") (pinfunction "E2_2") (pintype "passive"))
    )
    (net (code "91") (name "Net-(D3-I{slash}O2)") (class "Default")
      (node (ref "D3") (pin "2") (pinfunction "I/O2_2") (pintype "passive"))
      (node (ref "IC11") (pin "6") (pinfunction "CANL_6") (pintype "bidirectional"))
      (node (ref "J1") (pin "4") (pinfunction "4_4") (pintype "bidirectional"))
      (node (ref "R29") (pin "1") (pinfunction "1_1") (pintype "passive"))
    )
    (net (code "92") (name "Net-(D4-I{slash}O1)") (class "Default")
      (node (ref "D4") (pin "1") (pinfunction "I/O1_1") (pintype "passive"))
      (node (ref "IC15") (pin "6") (pinfunction "A_6") (pintype "bidirectional"))
      (node (ref "J4") (pin "2") (pinfunction "2_2") (pintype "bidirectional"))
      (node (ref "JP2") (pin "2") (pinfunction "E2_2") (pintype "passive"))
    )
    (net (code "93") (name "Net-(D4-I{slash}O2)") (class "Default")
      (node (ref "D4") (pin "2") (pinfunction "I/O2_2") (pintype "passive"))
      (node (ref "IC15") (pin "7") (pinfunction "B_7") (pintype "bidirectional"))
      (node (ref "J4") (pin "4") (pinfunction "4_4") (pintype "bidirectional"))
      (node (ref "R59") (pin "1") (pinfunction "1_1") (pintype "passive"))
    )
    (net (code "94") (name "Net-(IC1-RS)") (class "Default")
      (node (ref "IC1") (pin "8") (pinfunction "RS_8") (pintype "input"))
      (node (ref "R12") (pin "2") (pinfunction "2_2") (pintype "passive"))
    )
    (net (code "95") (name "Net-(IC1-RXD)") (class "Default")
      (node (ref "IC1") (pin "4") (pinfunction "RXD_4") (pintype "output"))
      (node (ref "R17") (pin "1") (pinfunction "1_1") (pintype "passive"))
    )
    (net (code "96") (name "Net-(IC9C-BOOT0)") (class "Default")
      (node (ref "IC9") (pin "138") (pinfunction "BOOT0_138") (pintype "passive"))
      (node (ref "JP4") (pin "2") (pinfunction "E2_2") (pintype "passive"))
      (node (ref "R4") (pin "1") (pinfunction "1_1") (pintype "passive"))
    )
    (net (code "97") (name "Net-(IC9C-PDR_ON)") (class "Default")
      (node (ref "IC9") (pin "143") (pinfunction "PDR_ON_143") (pintype "passive"))
      (node (ref "R97") (pin "1") (pinfunction "1_1") (pintype "passive"))
    )
    (net (code "98") (name "Net-(IC9C-PH0{slash}OSC_IN)") (class "Default")
      (node (ref "C89") (pin "2") (pinfunction "2_2") (pintype "passive"))
      (node (ref "IC9") (pin "23") (pinfunction "PH0/OSC_IN_23") (pintype "passive"))
      (node (ref "Q5") (pin "2") (pinfunction "OSC2_2") (pintype "passive"))
    )
    (net (code "99") (name "Net-(IC9C-PH1{slash}OSC_OUT)") (class "Default")
      (node (ref "C90") (pin "2") (pinfunction "2_2") (pintype "passive"))
      (node (ref "IC9") (pin "24") (pinfunction "PH1/OSC_OUT_24") (pintype "passive"))
      (node (ref "Q5") (pin "1") (pinfunction "OSC1_1") (pintype "passive"))
    )
    (net (code "100") (name "Net-(IC9C-VCAP1)") (class "Default")
      (node (ref "C29") (pin "1") (pinfunction "1_1") (pintype "passive"))
      (node (ref "IC9") (pin "71") (pinfunction "VCAP1_71") (pintype "passive"))
    )
    (net (code "101") (name "Net-(IC9C-VCAP2)") (class "Default")
      (node (ref "C28") (pin "1") (pinfunction "1_1") (pintype "passive"))
      (node (ref "IC9") (pin "106") (pinfunction "VCAP2_106") (pintype "passive"))
    )
    (net (code "102") (name "Net-(IC11-RS)") (class "Default")
      (node (ref "IC11") (pin "8") (pinfunction "RS_8") (pintype "input"))
      (node (ref "R14") (pin "2") (pinfunction "2_2") (pintype "passive"))
    )
    (net (code "103") (name "Net-(IC11-RXD)") (class "Default")
      (node (ref "IC11") (pin "4") (pinfunction "RXD_4") (pintype "output"))
      (node (ref "R53") (pin "1") (pinfunction "1_1") (pintype "passive"))
    )
    (net (code "104") (name "Net-(IC13-OUT)") (class "Default")
      (node (ref "C27") (pin "2") (pinfunction "2_2") (pintype "passive"))
      (node (ref "C31") (pin "1") (pinfunction "1_1") (pintype "passive"))
      (node (ref "IC13") (pin "2") (pinfunction "OUT_2") (pintype "power_in"))
      (node (ref "IC9") (pin "32") (pinfunction "VREF+_32") (pintype "passive"))
    )
    (net (code "105") (name "Net-(IC14-~{HOLD}{slash}IO3)") (class "Default")
      (node (ref "IC14") (pin "3") (pinfunction "~{WP}/IO2_3") (pintype "bidirectional"))
      (node (ref "IC14") (pin "7") (pinfunction "~{HOLD}/IO3_7") (pintype "bidirectional"))
      (node (ref "R70") (pin "1") (pinfunction "1_1") (pintype "passive"))
    )
    (net (code "106") (name "Net-(IC15-RO)") (class "Default")
      (node (ref "IC15") (pin "1") (pinfunction "RO_1") (pintype "output"))
      (node (ref "R64") (pin "2") (pinfunction "2_2") (pintype "passive"))
    )
    (net (code "107") (name "Net-(JP2-E1)") (class "Default")
      (node (ref "JP2") (pin "1") (pinfunction "E1_1") (pintype "passive"))
      (node (ref "R59") (pin "2") (pinfunction "2_2") (pintype "passive"))
    )
    (net (code "108") (name "Net-(JP3-E1)") (class "Default")
      (node (ref "JP3") (pin "1") (pinfunction "E1_1") (pintype "passive"))
      (node (ref "R29") (pin "2") (pinfunction "2_2") (pintype "passive"))
    )
    (net (code "109") (name "Net-(LD2A-A)") (class "Default")
      (node (ref "LD2") (pin "1") (pinfunction "A_1") (pintype "passive"))
      (node (ref "R124") (pin "1") (pinfunction "1_1") (pintype "passive"))
    )
    (net (code "110") (name "Net-(LD2B-A)") (class "Default")
      (node (ref "LD2") (pin "3") (pinfunction "A_3") (pintype "passive"))
      (node (ref "R96") (pin "1") (pinfunction "1_1") (pintype "passive"))
    )
    (net (code "111") (name "Net-(LD2C-A)") (class "Default")
      (node (ref "LD2") (pin "5") (pinfunction "A_5") (pintype "passive"))
      (node (ref "R109") (pin "1") (pinfunction "1_1") (pintype "passive"))
    )
    (net (code "112") (name "P3V3") (class "Default")
      (node (ref "C35") (pin "1") (pinfunction "1_1") (pintype "passive"))
      (node (ref "C36") (pin "1") (pinfunction "1_1") (pintype "passive"))
      (node (ref "C38") (pin "1") (pinfunction "1_1") (pintype "passive"))
      (node (ref "C39") (pin "1") (pinfunction "1_1") (pintype "passive"))
      (node (ref "C4") (pin "2") (pinfunction "2_2") (pintype "passive"))
      (node (ref "C40") (pin "1") (pinfunction "1_1") (pintype "passive"))
      (node (ref "C50") (pin "1") (pinfunction "1_1") (pintype "passive"))
      (node (ref "C58") (pin "1") (pinfunction "1_1") (pintype "passive"))
      (node (ref "C59") (pin "1") (pinfunction "1_1") (pintype "passive"))
      (node (ref "C67") (pin "1") (pinfunction "1_1") (pintype "passive"))
      (node (ref "C70") (pin "1") (pinfunction "1_1") (pintype "passive"))
      (node (ref "C72") (pin "1") (pinfunction "1_1") (pintype "passive"))
      (node (ref "C73") (pin "1") (pinfunction "1_1") (pintype "passive"))
      (node (ref "C74") (pin "1") (pinfunction "1_1") (pintype "passive"))
      (node (ref "C78") (pin "2") (pinfunction "2_2") (pintype "passive"))
      (node (ref "IC10") (pin "3") (pinfunction "~{MR}_3") (pintype "input"))
      (node (ref "IC10") (pin "4") (pinfunction "VCC_4") (pintype "power_in"))
      (node (ref "IC12") (pin "4") (pinfunction "VCC_4") (pintype "power_in"))
      (node (ref "IC13") (pin "1") (pinfunction "IN_1") (pintype "input"))
      (node (ref "IC14") (pin "8") (pinfunction "VCC_8") (pintype "power_in"))
      (node (ref "IC7") (pin "1") (pinfunction "E0_1") (pintype "input"))
      (node (ref "IC7") (pin "8") (pinfunction "VCC_8") (pintype "power_in"))
      (node (ref "IC9") (pin "108") (pinfunction "VDD_2_108") (pintype "passive"))
      (node (ref "IC9") (pin "121") (pinfunction "VDD_SDMMC_121") (pintype "passive"))
      (node (ref "IC9") (pin "131") (pinfunction "VDD_11_131") (pintype "passive"))
      (node (ref "IC9") (pin "144") (pinfunction "VDD_3_144") (pintype "passive"))
      (node (ref "IC9") (pin "17") (pinfunction "VDD_5_17") (pintype "passive"))
      (node (ref "IC9") (pin "30") (pinfunction "VDD_12_30") (pintype "passive"))
      (node (ref "IC9") (pin "39") (pinfunction "VDD_4_39") (pintype "passive"))
      (node (ref "IC9") (pin "52") (pinfunction "VDD_6_52") (pintype "passive"))
      (node (ref "IC9") (pin "6") (pinfunction "VBAT_6") (pintype "passive"))
      (node (ref "IC9") (pin "62") (pinfunction "VDD_7_62") (pintype "passive"))
      (node (ref "IC9") (pin "72") (pinfunction "VDD_1_72") (pintype "passive"))
      (node (ref "IC9") (pin "84") (pinfunction "VDD_8_84") (pintype "passive"))
      (node (ref "IC9") (pin "95") (pinfunction "VDD33_USB_95") (pintype "passive"))
      (node (ref "J2") (pin "4") (pinfunction "VDD_4") (pintype "power_in"))
      (node (ref "JP1") (pin "1") (pinfunction "1_1") (pintype "passive"))
      (node (ref "JP4") (pin "1") (pinfunction "E1_1") (pintype "passive"))
      (node (ref "L15") (pin "1") (pinfunction "1_1") (pintype "passive"))
      (node (ref "R1") (pin "1") (pinfunction "1_1") (pintype "passive"))
      (node (ref "R124") (pin "2") (pinfunction "2_2") (pintype "passive"))
      (node (ref "R13") (pin "1") (pinfunction "1_1") (pintype "passive"))
      (node (ref "R18") (pin "2") (pinfunction "2_2") (pintype "passive"))
      (node (ref "R2") (pin "1") (pinfunction "1_1") (pintype "passive"))
      (node (ref "R3") (pin "1") (pinfunction "1_1") (pintype "passive"))
      (node (ref "R69") (pin "2") (pinfunction "2_2") (pintype "passive"))
      (node (ref "R70") (pin "2") (pinfunction "2_2") (pintype "passive"))
      (node (ref "R97") (pin "2") (pinfunction "2_2") (pintype "passive"))
    )
    (net (code "113") (name "P5V0") (class "Default")
      (node (ref "C34") (pin "2") (pinfunction "2_2") (pintype "passive"))
      (node (ref "C41") (pin "2") (pinfunction "2_2") (pintype "passive"))
      (node (ref "C47") (pin "1") (pinfunction "1_1") (pintype "passive"))
      (node (ref "IC1") (pin "3") (pinfunction "VDD_3") (pintype "power_in"))
      (node (ref "IC11") (pin "3") (pinfunction "VDD_3") (pintype "power_in"))
      (node (ref "IC15") (pin "8") (pinfunction "VCC_8") (pintype "power_in"))
    )
    (net (code "114") (name "P12V0") (class "Default")
      (node (ref "J1") (pin "1") (pinfunction "1_1") (pintype "bidirectional"))
      (node (ref "J4") (pin "1") (pinfunction "1_1") (pintype "bidirectional"))
    )
    (net (code "115") (name "unconnected-(IC1-VREF-Pad5)") (class "Default")
      (node (ref "IC1") (pin "5") (pinfunction "VREF_5") (pintype "output"))
    )
    (net (code "116") (name "unconnected-(IC9A-PA0-Pad34)") (class "Default")
      (node (ref "IC9") (pin "34") (pinfunction "PA0_34") (pintype "passive"))
    )
    (net (code "117") (name "unconnected-(IC9A-PB0-Pad46)") (class "Default")
      (node (ref "IC9") (pin "46") (pinfunction "PB0_46") (pintype "passive"))
    )
    (net (code "118") (name "unconnected-(IC9A-PB1-Pad47)") (class "Default")
      (node (ref "IC9") (pin "47") (pinfunction "PB1_47") (pintype "passive"))
    )
    (net (code "119") (name "unconnected-(IC9A-PB2-Pad48)") (class "Default")
      (node (ref "IC9") (pin "48") (pinfunction "PB2_48") (pintype "passive"))
    )
    (net (code "120") (name "unconnected-(IC9A-PB5-Pad135)") (class "Default")
      (node (ref "IC9") (pin "135") (pinfunction "PB5_135") (pintype "passive"))
    )
    (net (code "121") (name "unconnected-(IC9A-PB10-Pad69)") (class "Default")
      (node (ref "IC9") (pin "69") (pinfunction "PB10_69") (pintype "passive"))
    )
    (net (code "122") (name "unconnected-(IC9A-PB11-Pad70)") (class "Default")
      (node (ref "IC9") (pin "70") (pinfunction "PB11_70") (pintype "passive"))
    )
    (net (code "123") (name "unconnected-(IC9A-PB12-Pad73)") (class "Default")
      (node (ref "IC9") (pin "73") (pinfunction "PB12_73") (pintype "passive"))
    )
    (net (code "124") (name "unconnected-(IC9A-PB14-Pad75)") (class "Default")
      (node (ref "IC9") (pin "75") (pinfunction "PB14_75") (pintype "passive"))
    )
    (net (code "125") (name "unconnected-(IC9A-PB15-Pad76)") (class "Default")
      (node (ref "IC9") (pin "76") (pinfunction "PB15_76") (pintype "passive"))
    )
    (net (code "126") (name "unconnected-(IC9A-PC0-Pad26)") (class "Default")
      (node (ref "IC9") (pin "26") (pinfunction "PC0_26") (pintype "passive"))
    )
    (net (code "127") (name "unconnected-(IC9A-PC6-Pad96)") (class "Default")
      (node (ref "IC9") (pin "96") (pinfunction "PC6_96") (pintype "passive"))
    )
    (net (code "128") (name "unconnected-(IC9A-PC7-Pad97)") (class "Default")
      (node (ref "IC9") (pin "97") (pinfunction "PC7_97") (pintype "passive"))
    )
    (net (code "129") (name "unconnected-(IC9A-PC13-Pad7)") (class "Default")
      (node (ref "IC9") (pin "7") (pinfunction "PC13_7") (pintype "passive"))
    )
    (net (code "130") (name "unconnected-(IC9A-PC14-OSC32_IN-Pad8)") (class "Default")
      (node (ref "IC9") (pin "8") (pinfunction "PC14-OSC32_IN_8") (pintype "passive"))
    )
    (net (code "131") (name "unconnected-(IC9A-PC15-OSC32_OUT-Pad9)") (class "Default")
      (node (ref "IC9") (pin "9") (pinfunction "PC15-OSC32_OUT_9") (pintype "passive"))
    )
    (net (code "132") (name "unconnected-(IC9B-PE11-Pad64)") (class "Default")
      (node (ref "IC9") (pin "64") (pinfunction "PE11_64") (pintype "passive"))
    )
    (net (code "133") (name "unconnected-(IC9B-PE13-Pad66)") (class "Default")
      (node (ref "IC9") (pin "66") (pinfunction "PE13_66") (pintype "passive"))
    )
    (net (code "134") (name "unconnected-(IC9B-PE14-Pad67)") (class "Default")
      (node (ref "IC9") (pin "67") (pinfunction "PE14_67") (pintype "passive"))
    )
    (net (code "135") (name "unconnected-(IC9B-PF8-Pad20)") (class "Default")
      (node (ref "IC9") (pin "20") (pinfunction "PF8_20") (pintype "passive"))
    )
    (net (code "136") (name "unconnected-(IC9B-PF9-Pad21)") (class "Default")
      (node (ref "IC9") (pin "21") (pinfunction "PF9_21") (pintype "passive"))
    )
    (net (code "137") (name "unconnected-(IC9B-PF10-Pad22)") (class "Default")
      (node (ref "IC9") (pin "22") (pinfunction "PF10_22") (pintype "passive"))
    )
    (net (code "138") (name "unconnected-(IC9B-PF11-Pad49)") (class "Default")
      (node (ref "IC9") (pin "49") (pinfunction "PF11_49") (pintype "passive"))
    )
    (net (code "139") (name "unconnected-(IC9B-PF12-Pad50)") (class "Default")
      (node (ref "IC9") (pin "50") (pinfunction "PF12_50") (pintype "passive"))
    )
    (net (code "140") (name "unconnected-(IC9B-PF13-Pad53)") (class "Default")
      (node (ref "IC9") (pin "53") (pinfunction "PF13_53") (pintype "passive"))
    )
    (net (code "141") (name "unconnected-(IC9B-PF14-Pad54)") (class "Default")
      (node (ref "IC9") (pin "54") (pinfunction "PF14_54") (pintype "passive"))
    )
    (net (code "142") (name "unconnected-(IC9B-PF15-Pad55)") (class "Default")
      (node (ref "IC9") (pin "55") (pinfunction "PF15_55") (pintype "passive"))
    )
    (net (code "143") (name "unconnected-(IC9B-PG8-Pad93)") (class "Default")
      (node (ref "IC9") (pin "93") (pinfunction "PG8_93") (pintype "passive"))
    )
    (net (code "144") (name "unconnected-(IC9B-PG9-Pad124)") (class "Default")
      (node (ref "IC9") (pin "124") (pinfunction "PG9_124") (pintype "passive"))
    )
    (net (code "145") (name "unconnected-(IC9B-PG10-Pad125)") (class "Default")
      (node (ref "IC9") (pin "125") (pinfunction "PG10_125") (pintype "passive"))
    )
    (net (code "146") (name "unconnected-(IC9B-PG12-Pad127)") (class "Default")
      (node (ref "IC9") (pin "127") (pinfunction "PG12_127") (pintype "passive"))
    )
    (net (code "147") (name "unconnected-(IC9B-PG14-Pad129)") (class "Default")
      (node (ref "IC9") (pin "129") (pinfunction "PG14_129") (pintype "passive"))
    )
    (net (code "148") (name "unconnected-(IC9B-PG15-Pad132)") (class "Default")
      (node (ref "IC9") (pin "132") (pinfunction "PG15_132") (pintype "passive"))
    )
    (net (code "149") (name "unconnected-(IC11-VREF-Pad5)") (class "Default")
      (node (ref "IC11") (pin "5") (pinfunction "VREF_5") (pintype "output"))
    )
    (net (code "150") (name "unconnected-(JP1-Pad7)") (class "Default")
      (node (ref "JP1") (pin "7") (pinfunction "7_7") (pintype "passive"))
    )
  )
)
